# MAX31856.net
KiCad netlist of a schematic drawn in EAGLE
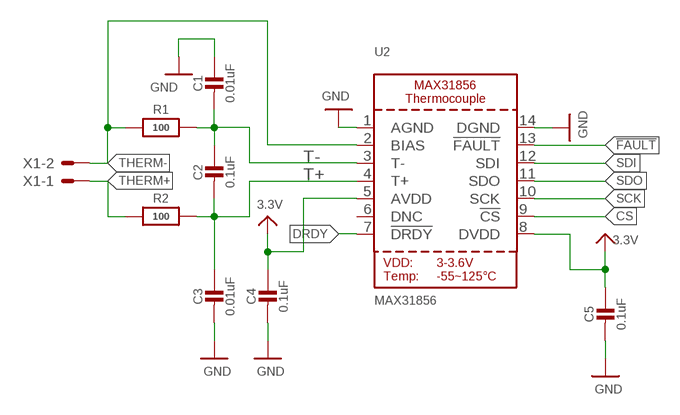
[diagram p0: schematic, sheet 1]

(export (version "E")
  (design (tool "Eeschema 10.0.6"))
  (components
    (comp (ref "C1")
      (value "0.01uF")
      (footprint "eagle-import:0805_10MGAP")
      (libsource (lib "eagle-import") (part "CAP_CERAMIC0805_10MGAP"))
    )
    (comp (ref "C2")
      (value "0.1uF")
      (footprint "eagle-import:0805-NO")
      (libsource (lib "eagle-import") (part "CAP_CERAMIC0805-NOOUTLINE"))
    )
    (comp (ref "C3")
      (value "0.01uF")
      (footprint "eagle-import:0805-NO")
      (libsource (lib "eagle-import") (part "CAP_CERAMIC0805-NOOUTLINE"))
    )
    (comp (ref "C4")
      (value "0.1uF")
      (footprint "eagle-import:0805-NO")
      (libsource (lib "eagle-import") (part "CAP_CERAMIC0805-NOOUTLINE"))
    )
    (comp (ref "C5")
      (value "0.1uF")
      (footprint "eagle-import:0805-NO")
      (libsource (lib "eagle-import") (part "CAP_CERAMIC0805-NOOUTLINE"))
    )
    (comp (ref "R1")
      (value "100")
      (footprint "eagle-import:0805-NO")
      (libsource (lib "eagle-import") (part "RESISTOR0805_NOOUTLINE"))
    )
    (comp (ref "R2")
      (value "100")
      (footprint "eagle-import:0805-NO")
      (libsource (lib "eagle-import") (part "RESISTOR0805_NOOUTLINE"))
    )
    (comp (ref "U2")
      (value "MAX31856")
      (footprint "eagle-import:TSSOP14")
      (libsource (lib "eagle-import") (part "MAX31856"))
    )
    (comp (ref "X1")
      (value "JST-XH-02-PIN-ROUND-PAD")
      (footprint "eagle-import:JST-XH-02-PACKAGE-ROUND-PAD")
      (libsource (lib "eagle-import") (part "JST-XH-02-PIN-ROUND-PAD"))
    )
  )
  (nets
    (net (code "1") (name "/T+") (class "Default")
      (node (ref "C2") (pin "2") (pinfunction "2_2") (pintype "passive"))
      (node (ref "C3") (pin "1") (pinfunction "1_1") (pintype "passive"))
      (node (ref "R2") (pin "2") (pinfunction "2_2") (pintype "passive"))
      (node (ref "U2") (pin "4") (pinfunction "T+_4") (pintype "input"))
    )
    (net (code "2") (name "/T-") (class "Default")
      (node (ref "C1") (pin "2") (pinfunction "2_2") (pintype "passive"))
      (node (ref "C2") (pin "1") (pinfunction "1_1") (pintype "passive"))
      (node (ref "R1") (pin "2") (pinfunction "2_2") (pintype "passive"))
      (node (ref "U2") (pin "3") (pinfunction "T-_3") (pintype "input"))
    )
    (net (code "3") (name "/~{FAULT}") (class "Default")
      (node (ref "U2") (pin "13") (pinfunction "~{FAULT}_13") (pintype "output"))
    )
    (net (code "4") (name "3.3V") (class "Default")
      (node (ref "C4") (pin "1") (pinfunction "1_1") (pintype "passive"))
      (node (ref "C5") (pin "1") (pinfunction "1_1") (pintype "passive"))
      (node (ref "U2") (pin "5") (pinfunction "AVDD_5") (pintype "power_in"))
      (node (ref "U2") (pin "8") (pinfunction "DVDD_8") (pintype "power_in"))
    )
    (net (code "5") (name "CS") (class "Default")
      (node (ref "U2") (pin "9") (pinfunction "~{CS}_9") (pintype "input"))
    )
    (net (code "6") (name "DRDY") (class "Default")
      (node (ref "U2") (pin "7") (pinfunction "~{DRDY}_7") (pintype "output"))
    )
    (net (code "7") (name "GND") (class "Default")
      (node (ref "C1") (pin "1") (pinfunction "1_1") (pintype "passive"))
      (node (ref "C3") (pin "2") (pinfunction "2_2") (pintype "passive"))
      (node (ref "C4") (pin "2") (pinfunction "2_2") (pintype "passive"))
      (node (ref "C5") (pin "2") (pinfunction "2_2") (pintype "passive"))
      (node (ref "U2") (pin "1") (pinfunction "AGND_1") (pintype "power_in"))
      (node (ref "U2") (pin "14") (pinfunction "DGND_14") (pintype "power_in"))
    )
    (net (code "8") (name "SCK") (class "Default")
      (node (ref "U2") (pin "10") (pinfunction "SCK_10") (pintype "input"))
    )
    (net (code "9") (name "SDI") (class "Default")
      (node (ref "U2") (pin "12") (pinfunction "SDI_12") (pintype "input"))
    )
    (net (code "10") (name "SDO") (class "Default")
      (node (ref "U2") (pin "11") (pinfunction "SDO_11") (pintype "output"))
    )
    (net (code "11") (name "THERM+") (class "Default")
      (node (ref "R2") (pin "1") (pinfunction "1_1") (pintype "passive"))
      (node (ref "X1") (pin "1") (pinfunction "S_1") (pintype "passive"))
    )
    (net (code "12") (name "THERM-") (class "Default")
      (node (ref "R1") (pin "1") (pinfunction "1_1") (pintype "passive"))
      (node (ref "U2") (pin "2") (pinfunction "BIAS_2") (pintype "power_in"))
      (node (ref "X1") (pin "2") (pinfunction "S_2") (pintype "passive"))
    )
    (net (code "13") (name "unconnected-(U2-DNC-Pad6)") (class "Default")
      (node (ref "U2") (pin "6") (pinfunction "DNC_6") (pintype "no_connect"))
    )
  )
)
